# bitsyled-v1_2.net
KiCad netlist of a schematic drawn in EAGLE
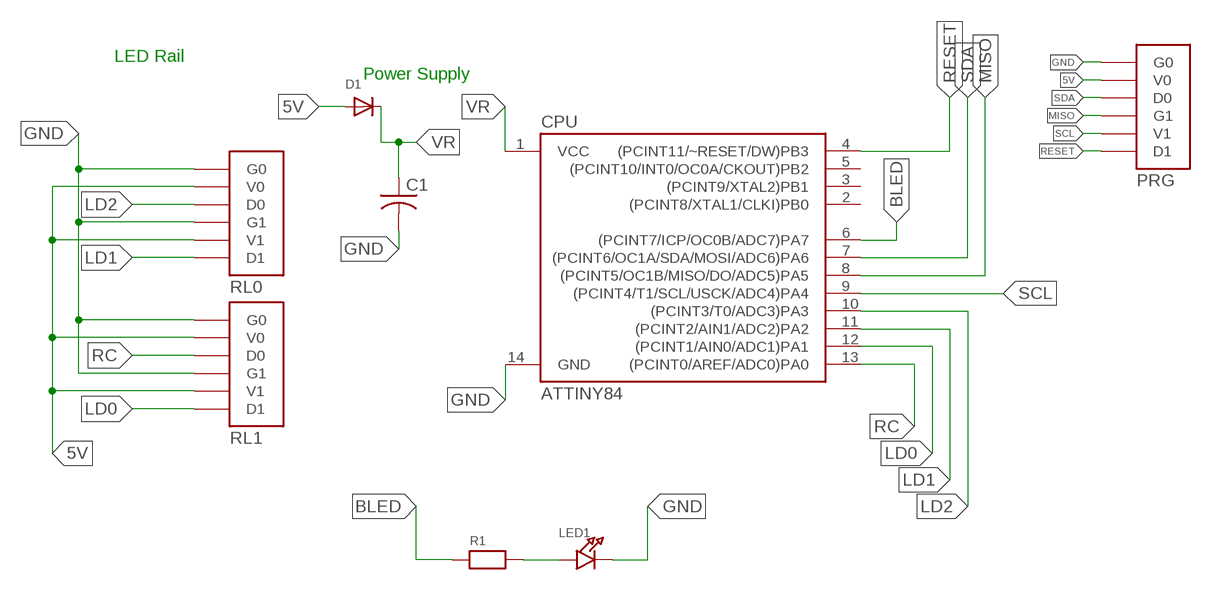
[diagram p0: schematic, sheet 1]

(export (version "E")
  (design (tool "Eeschema 10.0.6"))
  (components
    (comp (ref "C1")
      (value "C-USC0805")
      (footprint "eagle-import:C0805")
      (libsource (lib "eagle-import") (part "C-USC0805"))
    )
    (comp (ref "CPU")
      (value "ATTINY84")
      (footprint "eagle-import:SO14")
      (libsource (lib "eagle-import") (part "ATTINY84"))
    )
    (comp (ref "D1")
      (value "DIODESOD-123")
      (footprint "eagle-import:SOD-123")
      (libsource (lib "eagle-import") (part "DIODESOD-123"))
    )
    (comp (ref "LED1")
      (value "LED0805_NOOUTLINE")
      (footprint "eagle-import:CHIPLED_0805_NOOUTLINE")
      (libsource (lib "eagle-import") (part "LED0805_NOOUTLINE"))
    )
    (comp (ref "PRG")
      (value "BITSYLED_1X6_RAILPRG")
      (footprint "eagle-import:BITSYLED_1X6_RAIL_PRG")
      (libsource (lib "eagle-import") (part "BITSYLED_1X6_RAILPRG"))
    )
    (comp (ref "R1")
      (value "RESISTOR_0805")
      (footprint "eagle-import:_0805")
      (libsource (lib "eagle-import") (part "RESISTOR_0805"))
    )
    (comp (ref "RL0")
      (value "BITSYLED_1X6_RAILNORMAL")
      (footprint "eagle-import:BITSYLED_1X6_RAIL")
      (libsource (lib "eagle-import") (part "BITSYLED_1X6_RAILNORMAL"))
    )
    (comp (ref "RL1")
      (value "BITSYLED_1X6_RAILREVERSED")
      (footprint "eagle-import:BITSYLED_1X6_RAIL_R")
      (libsource (lib "eagle-import") (part "BITSYLED_1X6_RAILREVERSED"))
    )
  )
  (nets
    (net (code "1") (name "5V") (class "Default")
      (node (ref "D1") (pin "A") (pinfunction "A_A") (pintype "passive"))
      (node (ref "PRG") (pin "V0") (pinfunction "V0_V0") (pintype "input"))
      (node (ref "RL0") (pin "V0") (pinfunction "V0_V0") (pintype "input"))
      (node (ref "RL0") (pin "V1") (pinfunction "V1_V1") (pintype "input"))
      (node (ref "RL1") (pin "V0") (pinfunction "V0_V0") (pintype "input"))
      (node (ref "RL1") (pin "V1") (pinfunction "V1_V1") (pintype "input"))
    )
    (net (code "2") (name "BLED") (class "Default")
      (node (ref "CPU") (pin "6") (pinfunction "(PCINT7/ICP/OC0B/ADC7)PA7_6") (pintype "bidirectional"))
      (node (ref "R1") (pin "1") (pinfunction "1_1") (pintype "passive"))
    )
    (net (code "3") (name "GND") (class "Default")
      (node (ref "C1") (pin "2") (pinfunction "2_2") (pintype "passive"))
      (node (ref "CPU") (pin "14") (pinfunction "GND_14") (pintype "bidirectional"))
      (node (ref "LED1") (pin "C") (pinfunction "C_C") (pintype "passive"))
      (node (ref "PRG") (pin "G0") (pinfunction "G0_G0") (pintype "input"))
      (node (ref "RL0") (pin "G0") (pinfunction "G0_G0") (pintype "input"))
      (node (ref "RL0") (pin "G1") (pinfunction "G1_G1") (pintype "input"))
      (node (ref "RL1") (pin "G0") (pinfunction "G0_G0") (pintype "input"))
      (node (ref "RL1") (pin "G1") (pinfunction "G1_G1") (pintype "input"))
    )
    (net (code "4") (name "LD0") (class "Default")
      (node (ref "CPU") (pin "12") (pinfunction "(PCINT1/AIN0/ADC1)PA1_12") (pintype "bidirectional"))
      (node (ref "RL1") (pin "D1") (pinfunction "D1_D1") (pintype "bidirectional"))
    )
    (net (code "5") (name "LD1") (class "Default")
      (node (ref "CPU") (pin "11") (pinfunction "(PCINT2/AIN1/ADC2)PA2_11") (pintype "bidirectional"))
      (node (ref "RL0") (pin "D1") (pinfunction "D1_D1") (pintype "bidirectional"))
    )
    (net (code "6") (name "LD2") (class "Default")
      (node (ref "CPU") (pin "10") (pinfunction "(PCINT3/T0/ADC3)PA3_10") (pintype "bidirectional"))
      (node (ref "RL0") (pin "D0") (pinfunction "D0_D0") (pintype "bidirectional"))
    )
    (net (code "7") (name "MISO") (class "Default")
      (node (ref "CPU") (pin "8") (pinfunction "(PCINT5/OC1B/MISO/DO/ADC5)PA5_8") (pintype "bidirectional"))
      (node (ref "PRG") (pin "G1") (pinfunction "G1_G1") (pintype "input"))
    )
    (net (code "8") (name "Net-(LED1-PadA)") (class "Default")
      (node (ref "LED1") (pin "A") (pinfunction "A_A") (pintype "passive"))
      (node (ref "R1") (pin "2") (pinfunction "2_2") (pintype "passive"))
    )
    (net (code "9") (name "RC") (class "Default")
      (node (ref "CPU") (pin "13") (pinfunction "(PCINT0/AREF/ADC0)PA0_13") (pintype "bidirectional"))
      (node (ref "RL1") (pin "D0") (pinfunction "D0_D0") (pintype "bidirectional"))
    )
    (net (code "10") (name "RESET") (class "Default")
      (node (ref "CPU") (pin "4") (pinfunction "(PCINT11/~{RESET/DW})PB3_4") (pintype "bidirectional"))
      (node (ref "PRG") (pin "D1") (pinfunction "D1_D1") (pintype "bidirectional"))
    )
    (net (code "11") (name "SCL") (class "Default")
      (node (ref "CPU") (pin "9") (pinfunction "(PCINT4/T1/SCL/USCK/ADC4)PA4_9") (pintype "bidirectional"))
      (node (ref "PRG") (pin "V1") (pinfunction "V1_V1") (pintype "input"))
    )
    (net (code "12") (name "SDA") (class "Default")
      (node (ref "CPU") (pin "7") (pinfunction "(PCINT6/OC1A/SDA/MOSI/ADC6)PA6_7") (pintype "bidirectional"))
      (node (ref "PRG") (pin "D0") (pinfunction "D0_D0") (pintype "bidirectional"))
    )
    (net (code "13") (name "VR") (class "Default")
      (node (ref "C1") (pin "1") (pinfunction "1_1") (pintype "passive"))
      (node (ref "CPU") (pin "1") (pinfunction "VCC_1") (pintype "bidirectional"))
      (node (ref "D1") (pin "C") (pinfunction "C_C") (pintype "passive"))
    )
    (net (code "14") (name "unconnected-(CPU-(PCINT8{slash}XTAL1{slash}CLKI)PB0-Pad2)") (class "Default")
      (node (ref "CPU") (pin "2") (pinfunction "(PCINT8/XTAL1/CLKI)PB0_2") (pintype "bidirectional"))
    )
    (net (code "15") (name "unconnected-(CPU-(PCINT9{slash}XTAL2)PB1-Pad3)") (class "Default")
      (node (ref "CPU") (pin "3") (pinfunction "(PCINT9/XTAL2)PB1_3") (pintype "bidirectional"))
    )
    (net (code "16") (name "unconnected-(CPU-(PCINT10{slash}INT0{slash}OC0A{slash}CKOUT)PB2-Pad5)") (class "Default")
      (node (ref "CPU") (pin "5") (pinfunction "(PCINT10/INT0/OC0A/CKOUT)PB2_5") (pintype "bidirectional"))
    )
  )
)
